# routev8_2.net
KiCad netlist of a schematic drawn in EAGLE
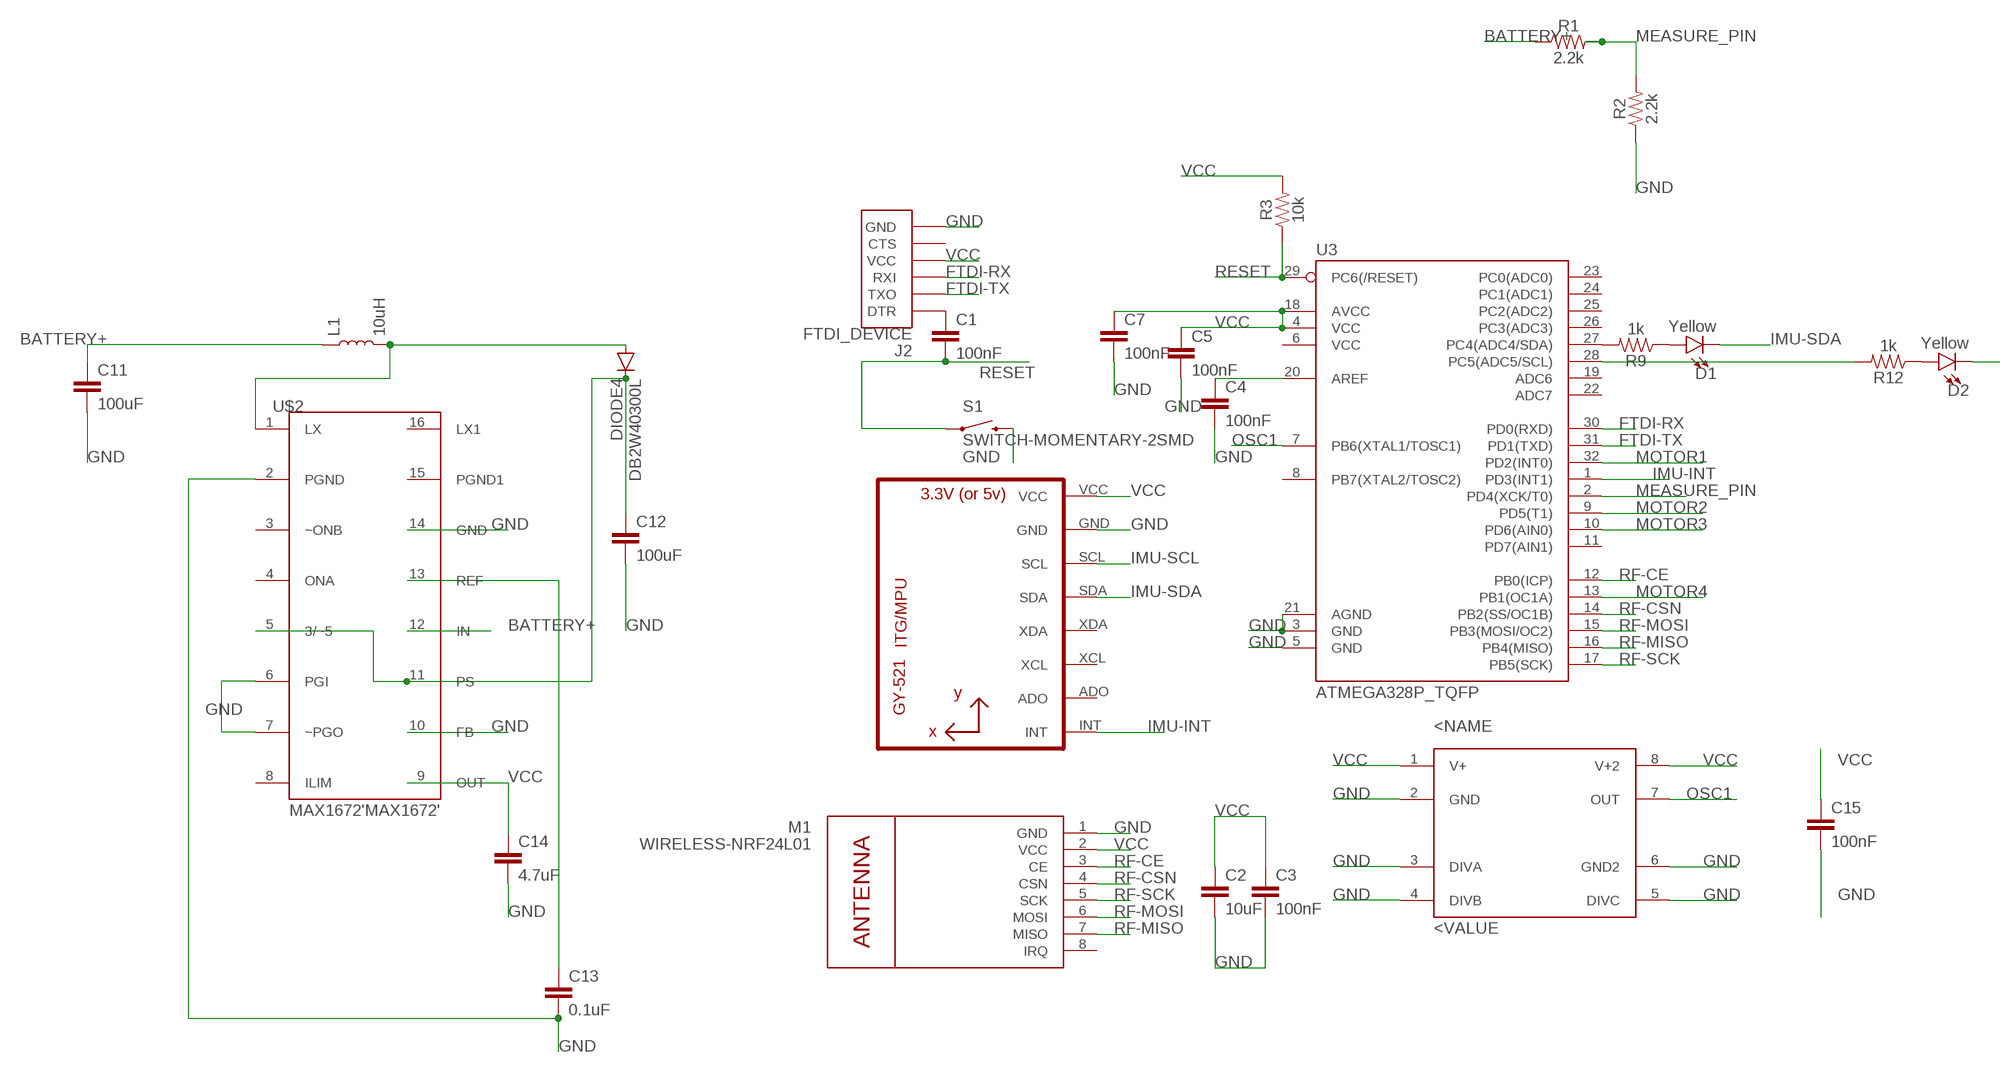
[diagram p0: schematic, sheet 1, part 1 of 2]
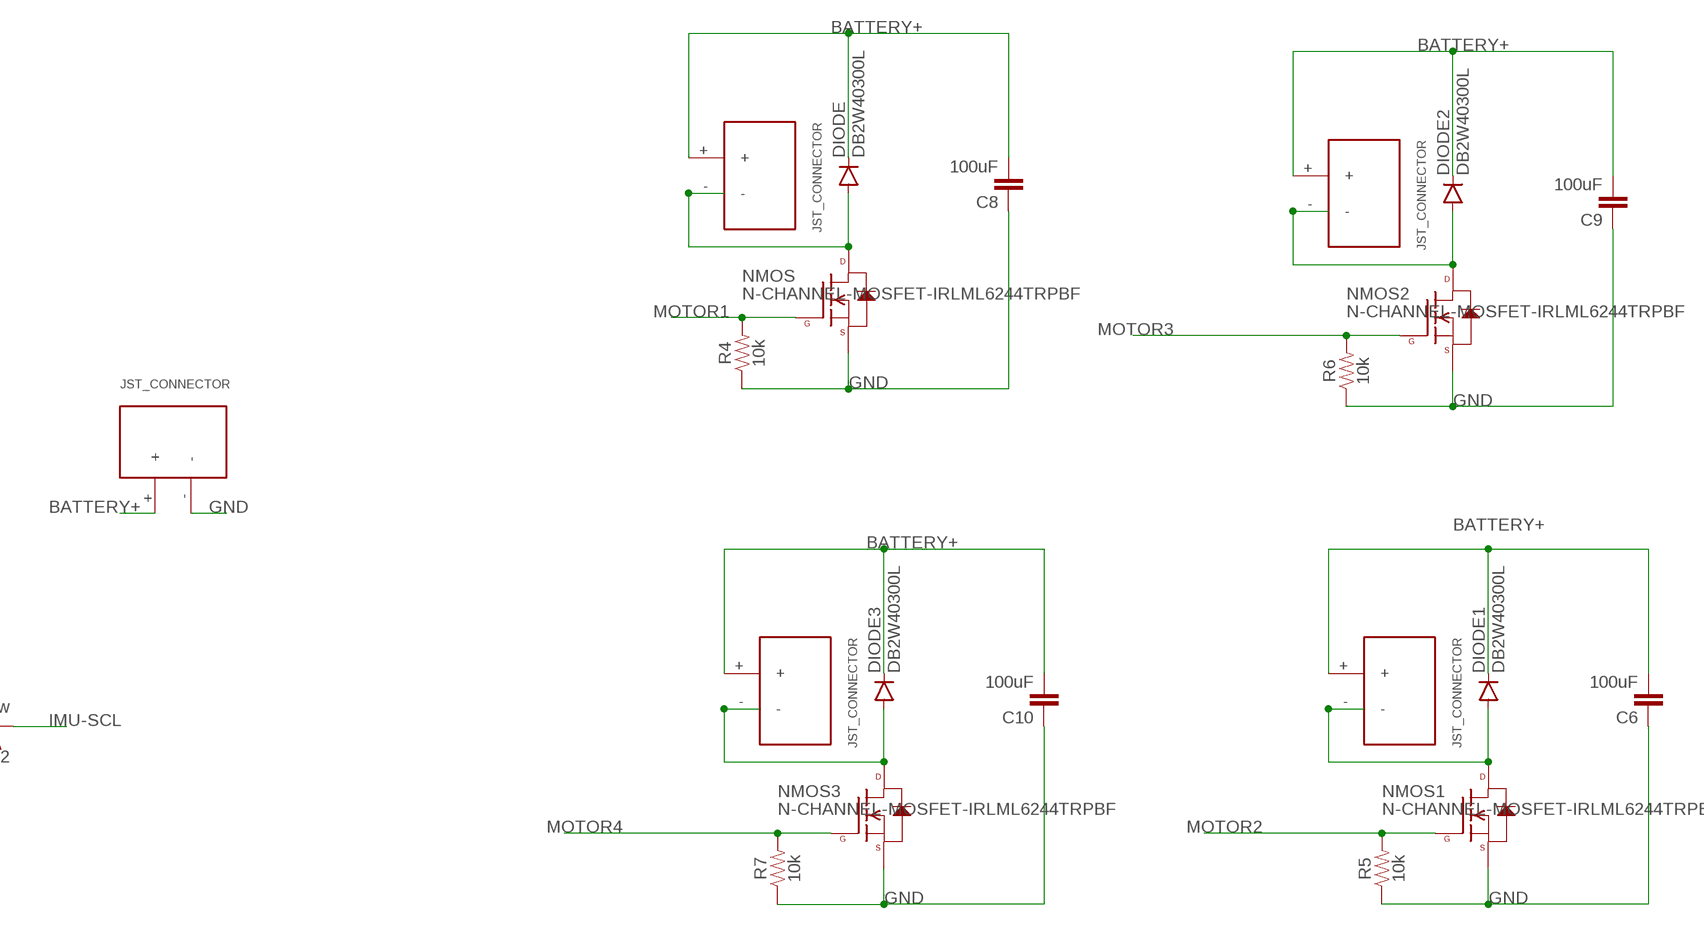
[diagram p1: schematic, sheet 1, part 2 of 2]

(export (version "E")
  (design (tool "Eeschema 10.0.6"))
  (components
    (comp (ref "C1")
      (value "100nF")
      (footprint "eagle-import:0603-CAP")
      (libsource (lib "eagle-import") (part "0.1UF-25V(+80/-20%)(0603)"))
    )
    (comp (ref "C2")
      (value "10uF")
      (footprint "eagle-import:0603-CAP")
      (libsource (lib "eagle-import") (part "CAP0603-CAP"))
    )
    (comp (ref "C3")
      (value "100nF")
      (footprint "eagle-import:0603-CAP")
      (libsource (lib "eagle-import") (part "CAP0603-CAP"))
    )
    (comp (ref "C4")
      (value "100nF")
      (footprint "eagle-import:0603-CAP")
      (libsource (lib "eagle-import") (part "CAP0603-CAP"))
    )
    (comp (ref "C5")
      (value "100nF")
      (footprint "eagle-import:0603-CAP")
      (libsource (lib "eagle-import") (part "CAP0603-CAP"))
    )
    (comp (ref "C6")
      (value "100uF")
      (footprint "eagle-import:0603-CAP")
      (libsource (lib "eagle-import") (part "CAP0603-CAP"))
    )
    (comp (ref "C7")
      (value "100nF")
      (footprint "eagle-import:0603-CAP")
      (libsource (lib "eagle-import") (part "CAP0603-CAP"))
    )
    (comp (ref "C8")
      (value "100uF")
      (footprint "eagle-import:0603-CAP")
      (libsource (lib "eagle-import") (part "CAP0603-CAP"))
    )
    (comp (ref "C9")
      (value "100uF")
      (footprint "eagle-import:0603-CAP")
      (libsource (lib "eagle-import") (part "CAP0603-CAP"))
    )
    (comp (ref "C10")
      (value "100uF")
      (footprint "eagle-import:0603-CAP")
      (libsource (lib "eagle-import") (part "CAP0603-CAP"))
    )
    (comp (ref "C11")
      (value "100uF")
      (footprint "eagle-import:0603-CAP")
      (libsource (lib "eagle-import") (part "CAP0603-CAP"))
    )
    (comp (ref "C12")
      (value "100uF")
      (footprint "eagle-import:0603-CAP")
      (libsource (lib "eagle-import") (part "CAP0603-CAP"))
    )
    (comp (ref "C13")
      (value "0.1uF")
      (footprint "eagle-import:0603-CAP")
      (libsource (lib "eagle-import") (part "CAP0603-CAP"))
    )
    (comp (ref "C14")
      (value "4.7uF")
      (footprint "eagle-import:0603-CAP")
      (libsource (lib "eagle-import") (part "CAP0603-CAP"))
    )
    (comp (ref "C15")
      (value "100nF")
      (footprint "eagle-import:0603-CAP")
      (libsource (lib "eagle-import") (part "0.1UF-25V(+80/-20%)(0603)"))
    )
    (comp (ref "D1")
      (value "Yellow")
      (footprint "eagle-import:LED-1206")
      (libsource (lib "eagle-import") (part "LED-YELLOWLILYPAD"))
    )
    (comp (ref "D2")
      (value "Yellow")
      (footprint "eagle-import:LED-1206")
      (libsource (lib "eagle-import") (part "LED-YELLOWLILYPAD"))
    )
    (comp (ref "DIODE")
      (value "DB2W40300L")
      (footprint "eagle-import:MINI2-F3-B")
      (libsource (lib "eagle-import") (part "DB2W40300L"))
    )
    (comp (ref "DIODE1")
      (value "DB2W40300L")
      (footprint "eagle-import:MINI2-F3-B")
      (libsource (lib "eagle-import") (part "DB2W40300L"))
    )
    (comp (ref "DIODE2")
      (value "DB2W40300L")
      (footprint "eagle-import:MINI2-F3-B")
      (libsource (lib "eagle-import") (part "DB2W40300L"))
    )
    (comp (ref "DIODE3")
      (value "DB2W40300L")
      (footprint "eagle-import:MINI2-F3-B")
      (libsource (lib "eagle-import") (part "DB2W40300L"))
    )
    (comp (ref "DIODE4")
      (value "DB2W40300L")
      (footprint "eagle-import:MINI2-F3-B")
      (libsource (lib "eagle-import") (part "DB2W40300L"))
    )
    (comp (ref "J2")
      (value "FTDI_DEVICE")
      (footprint "eagle-import:FTDI_DEVICE_SIDE")
      (libsource (lib "eagle-import") (part "FTDI_DEVICE"))
    )
    (comp (ref "L1")
      (value "10uH")
      (footprint "eagle-import:0603")
      (libsource (lib "eagle-import") (part "INDUCTOR-0603-33NH"))
    )
    (comp (ref "M1")
      (value "WIRELESS-NRF24L01")
      (footprint "eagle-import:WIRELESS-NRF24L01")
      (libsource (lib "eagle-import") (part "WIRELESS-NRF24L01"))
    )
    (comp (ref "MOTOR")
      (value "JST_CONNECTOR_FEMALE")
      (footprint "eagle-import:JST_CONNECTOR_FEMALE")
      (libsource (lib "eagle-import") (part "JST_CONNECTOR_FEMALE"))
    )
    (comp (ref "MOTOR1")
      (value "JST_CONNECTOR_FEMALE")
      (footprint "eagle-import:JST_CONNECTOR_FEMALE")
      (libsource (lib "eagle-import") (part "JST_CONNECTOR_FEMALE"))
    )
    (comp (ref "MOTOR2")
      (value "JST_CONNECTOR_FEMALE")
      (footprint "eagle-import:JST_CONNECTOR_FEMALE")
      (libsource (lib "eagle-import") (part "JST_CONNECTOR_FEMALE"))
    )
    (comp (ref "MOTOR3")
      (value "JST_CONNECTOR_FEMALE")
      (footprint "eagle-import:JST_CONNECTOR_FEMALE")
      (libsource (lib "eagle-import") (part "JST_CONNECTOR_FEMALE"))
    )
    (comp (ref "NMOS")
      (value "N-CHANNEL-MOSFET-IRLML6244TRPBF")
      (footprint "eagle-import:SOT23-3")
      (libsource (lib "eagle-import") (part "N-CHANNEL-MOSFET-IRLML6244TRPBF"))
    )
    (comp (ref "NMOS1")
      (value "N-CHANNEL-MOSFET-IRLML6244TRPBF")
      (footprint "eagle-import:SOT23-3")
      (libsource (lib "eagle-import") (part "N-CHANNEL-MOSFET-IRLML6244TRPBF"))
    )
    (comp (ref "NMOS2")
      (value "N-CHANNEL-MOSFET-IRLML6244TRPBF")
      (footprint "eagle-import:SOT23-3")
      (libsource (lib "eagle-import") (part "N-CHANNEL-MOSFET-IRLML6244TRPBF"))
    )
    (comp (ref "NMOS3")
      (value "N-CHANNEL-MOSFET-IRLML6244TRPBF")
      (footprint "eagle-import:SOT23-3")
      (libsource (lib "eagle-import") (part "N-CHANNEL-MOSFET-IRLML6244TRPBF"))
    )
    (comp (ref "R1")
      (value "2.2k")
      (footprint "eagle-import:0603")
      (libsource (lib "eagle-import") (part "2.2KOHM-0603-1/10W-1%"))
    )
    (comp (ref "R2")
      (value "2.2k")
      (footprint "eagle-import:0603")
      (libsource (lib "eagle-import") (part "2.2KOHM-0603-1/10W-1%"))
    )
    (comp (ref "R3")
      (value "10k")
      (footprint "eagle-import:0603")
      (libsource (lib "eagle-import") (part "2.2KOHM-0603-1/10W-1%"))
    )
    (comp (ref "R4")
      (value "10k")
      (footprint "eagle-import:0603")
      (libsource (lib "eagle-import") (part "2.2KOHM-0603-1/10W-1%"))
    )
    (comp (ref "R5")
      (value "10k")
      (footprint "eagle-import:0603")
      (libsource (lib "eagle-import") (part "2.2KOHM-0603-1/10W-1%"))
    )
    (comp (ref "R6")
      (value "10k")
      (footprint "eagle-import:0603")
      (libsource (lib "eagle-import") (part "2.2KOHM-0603-1/10W-1%"))
    )
    (comp (ref "R7")
      (value "10k")
      (footprint "eagle-import:0603")
      (libsource (lib "eagle-import") (part "2.2KOHM-0603-1/10W-1%"))
    )
    (comp (ref "R9")
      (value "1k")
      (footprint "eagle-import:0603")
      (libsource (lib "eagle-import") (part "2.2KOHM-0603-1/10W-1%"))
    )
    (comp (ref "R12")
      (value "1k")
      (footprint "eagle-import:0603")
      (libsource (lib "eagle-import") (part "2.2KOHM-0603-1/10W-1%"))
    )
    (comp (ref "S1")
      (value "SWITCH-MOMENTARY-2SMD")
      (footprint "eagle-import:TACTILE-SWITCH-SMD")
      (libsource (lib "eagle-import") (part "SWITCH-MOMENTARY-2SMD"))
    )
    (comp (ref "U$1")
      (value "JST_CONNECTOR_FEMALE")
      (footprint "eagle-import:JST_CONNECTOR_FEMALE")
      (libsource (lib "eagle-import") (part "JST_CONNECTOR_FEMALE"))
    )
    (comp (ref "U$2")
      (value "MAX1672'MAX1672'")
      (footprint "eagle-import:21-0055H_16")
      (libsource (lib "eagle-import") (part "MAX1672'MAX1672'"))
    )
    (comp (ref "U$3")
      (value "LTC6930CMS8-8.19LTC6930CMS8-8.19")
      (footprint "eagle-import:SOP65P490X110-8N")
      (libsource (lib "eagle-import") (part "LTC6930CMS8-8.19LTC6930CMS8-8.19"))
    )
    (comp (ref "U2")
      (value "GY-521MPU6050")
      (footprint "eagle-import:GY-521")
      (libsource (lib "eagle-import") (part "GY-521MPU6050"))
    )
    (comp (ref "U3")
      (value "ATMEGA328P_TQFP")
      (footprint "eagle-import:TQFP32-08")
      (libsource (lib "eagle-import") (part "ATMEGA328P_TQFP"))
    )
  )
  (nets
    (net (code "1") (name "BATTERY+") (class "Default")
      (node (ref "C10") (pin "2") (pinfunction "2_2") (pintype "passive"))
      (node (ref "C11") (pin "1") (pinfunction "1_1") (pintype "passive"))
      (node (ref "C6") (pin "2") (pinfunction "2_2") (pintype "passive"))
      (node (ref "C8") (pin "2") (pinfunction "2_2") (pintype "passive"))
      (node (ref "C9") (pin "2") (pinfunction "2_2") (pintype "passive"))
      (node (ref "DIODE") (pin "NEG") (pinfunction "GPIN_NEG") (pintype "passive"))
      (node (ref "DIODE1") (pin "NEG") (pinfunction "GPIN_NEG") (pintype "passive"))
      (node (ref "DIODE2") (pin "NEG") (pinfunction "GPIN_NEG") (pintype "passive"))
      (node (ref "DIODE3") (pin "NEG") (pinfunction "GPIN_NEG") (pintype "passive"))
      (node (ref "L1") (pin "1") (pinfunction "1_1") (pintype "passive"))
      (node (ref "MOTOR") (pin "+") (pinfunction "+_+") (pintype "bidirectional"))
      (node (ref "MOTOR1") (pin "+") (pinfunction "+_+") (pintype "bidirectional"))
      (node (ref "MOTOR2") (pin "+") (pinfunction "+_+") (pintype "bidirectional"))
      (node (ref "MOTOR3") (pin "+") (pinfunction "+_+") (pintype "bidirectional"))
      (node (ref "R1") (pin "1") (pinfunction "1_1") (pintype "passive"))
      (node (ref "U$1") (pin "+") (pinfunction "+_+") (pintype "bidirectional"))
      (node (ref "U$2") (pin "12") (pinfunction "IN_12") (pintype "bidirectional"))
    )
    (net (code "2") (name "FTDI-RX") (class "Default")
      (node (ref "J2") (pin "P$3") (pinfunction "RXI_P$3") (pintype "bidirectional"))
      (node (ref "U3") (pin "30") (pinfunction "PD0(RXD)_30") (pintype "bidirectional"))
    )
    (net (code "3") (name "FTDI-TX") (class "Default")
      (node (ref "J2") (pin "P$2") (pinfunction "TXO_P$2") (pintype "bidirectional"))
      (node (ref "U3") (pin "31") (pinfunction "PD1(TXD)_31") (pintype "bidirectional"))
    )
    (net (code "4") (name "GND") (class "Default")
      (node (ref "C10") (pin "1") (pinfunction "1_1") (pintype "passive"))
      (node (ref "C11") (pin "2") (pinfunction "2_2") (pintype "passive"))
      (node (ref "C12") (pin "2") (pinfunction "2_2") (pintype "passive"))
      (node (ref "C13") (pin "2") (pinfunction "2_2") (pintype "passive"))
      (node (ref "C14") (pin "2") (pinfunction "2_2") (pintype "passive"))
      (node (ref "C15") (pin "2") (pinfunction "2_2") (pintype "passive"))
      (node (ref "C2") (pin "2") (pinfunction "2_2") (pintype "passive"))
      (node (ref "C3") (pin "2") (pinfunction "2_2") (pintype "passive"))
      (node (ref "C4") (pin "2") (pinfunction "2_2") (pintype "passive"))
      (node (ref "C5") (pin "2") (pinfunction "2_2") (pintype "passive"))
      (node (ref "C6") (pin "1") (pinfunction "1_1") (pintype "passive"))
      (node (ref "C7") (pin "2") (pinfunction "2_2") (pintype "passive"))
      (node (ref "C8") (pin "1") (pinfunction "1_1") (pintype "passive"))
      (node (ref "C9") (pin "1") (pinfunction "1_1") (pintype "passive"))
      (node (ref "J2") (pin "P$6") (pinfunction "GND_P$6") (pintype "bidirectional"))
      (node (ref "M1") (pin "1") (pinfunction "GND_1") (pintype "power_in"))
      (node (ref "NMOS") (pin "2") (pinfunction "S_2") (pintype "passive"))
      (node (ref "NMOS1") (pin "2") (pinfunction "S_2") (pintype "passive"))
      (node (ref "NMOS2") (pin "2") (pinfunction "S_2") (pintype "passive"))
      (node (ref "NMOS3") (pin "2") (pinfunction "S_2") (pintype "passive"))
      (node (ref "R2") (pin "1") (pinfunction "1_1") (pintype "passive"))
      (node (ref "R4") (pin "1") (pinfunction "1_1") (pintype "passive"))
      (node (ref "R5") (pin "1") (pinfunction "1_1") (pintype "passive"))
      (node (ref "R6") (pin "1") (pinfunction "1_1") (pintype "passive"))
      (node (ref "R7") (pin "1") (pinfunction "1_1") (pintype "passive"))
      (node (ref "S1") (pin "3") (pinfunction "2_3") (pintype "passive"))
      (node (ref "U$1") (pin "-") (pinfunction "-_-") (pintype "bidirectional"))
      (node (ref "U$2") (pin "10") (pinfunction "FB_10") (pintype "bidirectional"))
      (node (ref "U$2") (pin "14") (pinfunction "GND_14") (pintype "bidirectional"))
      (node (ref "U$2") (pin "2") (pinfunction "PGND_2") (pintype "bidirectional"))
      (node (ref "U$2") (pin "6") (pinfunction "PGI_6") (pintype "bidirectional"))
      (node (ref "U$2") (pin "7") (pinfunction "~{PGO}_7") (pintype "bidirectional"))
      (node (ref "U$3") (pin "2") (pinfunction "GND_2") (pintype "bidirectional"))
      (node (ref "U$3") (pin "3") (pinfunction "DIVA_3") (pintype "bidirectional"))
      (node (ref "U$3") (pin "4") (pinfunction "DIVB_4") (pintype "bidirectional"))
      (node (ref "U$3") (pin "5") (pinfunction "DIVC_5") (pintype "bidirectional"))
      (node (ref "U$3") (pin "6") (pinfunction "GND2_6") (pintype "bidirectional"))
      (node (ref "U2") (pin "GND") (pinfunction "GND_GND") (pintype "bidirectional"))
      (node (ref "U3") (pin "21") (pinfunction "AGND_21") (pintype "bidirectional"))
      (node (ref "U3") (pin "3") (pinfunction "GND_3") (pintype "bidirectional"))
      (node (ref "U3") (pin "5") (pinfunction "GND_5") (pintype "bidirectional"))
    )
    (net (code "5") (name "IMU-INT") (class "Default")
      (node (ref "U2") (pin "INT") (pinfunction "INT_INT") (pintype "bidirectional"))
      (node (ref "U3") (pin "1") (pinfunction "PD3(INT1)_1") (pintype "bidirectional"))
    )
    (net (code "6") (name "IMU-SCL") (class "Default")
      (node (ref "D2") (pin "C") (pinfunction "C_C") (pintype "passive"))
      (node (ref "U2") (pin "SCL") (pinfunction "SCL_SCL") (pintype "bidirectional"))
    )
    (net (code "7") (name "IMU-SDA") (class "Default")
      (node (ref "D1") (pin "C") (pinfunction "C_C") (pintype "passive"))
      (node (ref "U2") (pin "SDA") (pinfunction "SDA_SDA") (pintype "bidirectional"))
    )
    (net (code "8") (name "MEASURE_PIN") (class "Default")
      (node (ref "R1") (pin "2") (pinfunction "2_2") (pintype "passive"))
      (node (ref "R2") (pin "2") (pinfunction "2_2") (pintype "passive"))
      (node (ref "U3") (pin "2") (pinfunction "PD4(XCK/T0)_2") (pintype "bidirectional"))
    )
    (net (code "9") (name "MOTOR1") (class "Default")
      (node (ref "NMOS") (pin "1") (pinfunction "G_1") (pintype "passive"))
      (node (ref "R4") (pin "2") (pinfunction "2_2") (pintype "passive"))
      (node (ref "U3") (pin "32") (pinfunction "PD2(INT0)_32") (pintype "bidirectional"))
    )
    (net (code "10") (name "MOTOR2") (class "Default")
      (node (ref "NMOS1") (pin "1") (pinfunction "G_1") (pintype "passive"))
      (node (ref "R5") (pin "2") (pinfunction "2_2") (pintype "passive"))
      (node (ref "U3") (pin "9") (pinfunction "PD5(T1)_9") (pintype "bidirectional"))
    )
    (net (code "11") (name "MOTOR3") (class "Default")
      (node (ref "NMOS2") (pin "1") (pinfunction "G_1") (pintype "passive"))
      (node (ref "R6") (pin "2") (pinfunction "2_2") (pintype "passive"))
      (node (ref "U3") (pin "10") (pinfunction "PD6(AIN0)_10") (pintype "bidirectional"))
    )
    (net (code "12") (name "MOTOR4") (class "Default")
      (node (ref "NMOS3") (pin "1") (pinfunction "G_1") (pintype "passive"))
      (node (ref "R7") (pin "2") (pinfunction "2_2") (pintype "passive"))
      (node (ref "U3") (pin "13") (pinfunction "PB1(OC1A)_13") (pintype "bidirectional"))
    )
    (net (code "13") (name "Net-(D1-PadA)") (class "Default")
      (node (ref "D1") (pin "A") (pinfunction "A_A") (pintype "passive"))
      (node (ref "R9") (pin "1") (pinfunction "1_1") (pintype "passive"))
    )
    (net (code "14") (name "Net-(D2-PadA)") (class "Default")
      (node (ref "D2") (pin "A") (pinfunction "A_A") (pintype "passive"))
      (node (ref "R12") (pin "1") (pinfunction "1_1") (pintype "passive"))
    )
    (net (code "15") (name "Net-(DIODE-PPIN)") (class "Default")
      (node (ref "DIODE") (pin "POS") (pinfunction "PPIN_POS") (pintype "passive"))
      (node (ref "MOTOR") (pin "-") (pinfunction "-_-") (pintype "bidirectional"))
      (node (ref "NMOS") (pin "3") (pinfunction "D_3") (pintype "passive"))
    )
    (net (code "16") (name "Net-(DIODE1-PPIN)") (class "Default")
      (node (ref "DIODE1") (pin "POS") (pinfunction "PPIN_POS") (pintype "passive"))
      (node (ref "MOTOR1") (pin "-") (pinfunction "-_-") (pintype "bidirectional"))
      (node (ref "NMOS1") (pin "3") (pinfunction "D_3") (pintype "passive"))
    )
    (net (code "17") (name "Net-(DIODE2-PPIN)") (class "Default")
      (node (ref "DIODE2") (pin "POS") (pinfunction "PPIN_POS") (pintype "passive"))
      (node (ref "MOTOR2") (pin "-") (pinfunction "-_-") (pintype "bidirectional"))
      (node (ref "NMOS2") (pin "3") (pinfunction "D_3") (pintype "passive"))
    )
    (net (code "18") (name "Net-(DIODE3-PPIN)") (class "Default")
      (node (ref "DIODE3") (pin "POS") (pinfunction "PPIN_POS") (pintype "passive"))
      (node (ref "MOTOR3") (pin "-") (pinfunction "-_-") (pintype "bidirectional"))
      (node (ref "NMOS3") (pin "3") (pinfunction "D_3") (pintype "passive"))
    )
    (net (code "19") (name "Net-(DIODE4-GPIN)") (class "Default")
      (node (ref "C12") (pin "1") (pinfunction "1_1") (pintype "passive"))
      (node (ref "DIODE4") (pin "NEG") (pinfunction "GPIN_NEG") (pintype "passive"))
      (node (ref "U$2") (pin "11") (pinfunction "PS_11") (pintype "bidirectional"))
      (node (ref "U$2") (pin "5") (pinfunction "3/~{5}_5") (pintype "bidirectional"))
    )
    (net (code "20") (name "Net-(DIODE4-PPIN)") (class "Default")
      (node (ref "DIODE4") (pin "POS") (pinfunction "PPIN_POS") (pintype "passive"))
      (node (ref "L1") (pin "2") (pinfunction "2_2") (pintype "passive"))
      (node (ref "U$2") (pin "1") (pinfunction "LX_1") (pintype "bidirectional"))
    )
    (net (code "21") (name "Net-(J2-DTR)") (class "Default")
      (node (ref "C1") (pin "1") (pinfunction "1_1") (pintype "passive"))
      (node (ref "J2") (pin "P$1") (pinfunction "DTR_P$1") (pintype "bidirectional"))
    )
    (net (code "22") (name "Net-(U$2-REF)") (class "Default")
      (node (ref "C13") (pin "1") (pinfunction "1_1") (pintype "passive"))
      (node (ref "U$2") (pin "13") (pinfunction "REF_13") (pintype "bidirectional"))
    )
    (net (code "23") (name "Net-(U3-AREF)") (class "Default")
      (node (ref "C4") (pin "1") (pinfunction "1_1") (pintype "passive"))
      (node (ref "U3") (pin "20") (pinfunction "AREF_20") (pintype "bidirectional"))
    )
    (net (code "24") (name "Net-(U3-PC4(ADC4{slash}SDA))") (class "Default")
      (node (ref "R9") (pin "2") (pinfunction "2_2") (pintype "passive"))
      (node (ref "U3") (pin "27") (pinfunction "PC4(ADC4/SDA)_27") (pintype "bidirectional"))
    )
    (net (code "25") (name "Net-(U3-PC5(ADC5{slash}SCL))") (class "Default")
      (node (ref "R12") (pin "2") (pinfunction "2_2") (pintype "passive"))
      (node (ref "U3") (pin "28") (pinfunction "PC5(ADC5/SCL)_28") (pintype "bidirectional"))
    )
    (net (code "26") (name "OSC1") (class "Default")
      (node (ref "U$3") (pin "7") (pinfunction "OUT_7") (pintype "bidirectional"))
      (node (ref "U3") (pin "7") (pinfunction "PB6(XTAL1/TOSC1)_7") (pintype "bidirectional"))
    )
    (net (code "27") (name "RESET") (class "Default")
      (node (ref "C1") (pin "2") (pinfunction "2_2") (pintype "passive"))
      (node (ref "R3") (pin "1") (pinfunction "1_1") (pintype "passive"))
      (node (ref "S1") (pin "1") (pinfunction "1_1") (pintype "passive"))
      (node (ref "U3") (pin "29") (pinfunction "PC6(/RESET)_29") (pintype "bidirectional"))
    )
    (net (code "28") (name "RF-CE") (class "Default")
      (node (ref "M1") (pin "3") (pinfunction "CE_3") (pintype "bidirectional"))
      (node (ref "U3") (pin "12") (pinfunction "PB0(ICP)_12") (pintype "bidirectional"))
    )
    (net (code "29") (name "RF-CSN") (class "Default")
      (node (ref "M1") (pin "4") (pinfunction "CSN_4") (pintype "bidirectional"))
      (node (ref "U3") (pin "14") (pinfunction "PB2(SS/OC1B)_14") (pintype "bidirectional"))
    )
    (net (code "30") (name "RF-MISO") (class "Default")
      (node (ref "M1") (pin "7") (pinfunction "MISO_7") (pintype "bidirectional"))
      (node (ref "U3") (pin "16") (pinfunction "PB4(MISO)_16") (pintype "bidirectional"))
    )
    (net (code "31") (name "RF-MOSI") (class "Default")
      (node (ref "M1") (pin "6") (pinfunction "MOSI_6") (pintype "bidirectional"))
      (node (ref "U3") (pin "15") (pinfunction "PB3(MOSI/OC2)_15") (pintype "bidirectional"))
    )
    (net (code "32") (name "RF-SCK") (class "Default")
      (node (ref "M1") (pin "5") (pinfunction "SCK_5") (pintype "bidirectional"))
      (node (ref "U3") (pin "17") (pinfunction "PB5(SCK)_17") (pintype "bidirectional"))
    )
    (net (code "33") (name "VCC") (class "Default")
      (node (ref "C14") (pin "1") (pinfunction "1_1") (pintype "passive"))
      (node (ref "C15") (pin "1") (pinfunction "1_1") (pintype "passive"))
      (node (ref "C2") (pin "1") (pinfunction "1_1") (pintype "passive"))
      (node (ref "C3") (pin "1") (pinfunction "1_1") (pintype "passive"))
      (node (ref "C5") (pin "1") (pinfunction "1_1") (pintype "passive"))
      (node (ref "C7") (pin "1") (pinfunction "1_1") (pintype "passive"))
      (node (ref "J2") (pin "P$4") (pinfunction "VCC_P$4") (pintype "bidirectional"))
      (node (ref "M1") (pin "2") (pinfunction "VCC_2") (pintype "power_in"))
      (node (ref "R3") (pin "2") (pinfunction "2_2") (pintype "passive"))
      (node (ref "U$2") (pin "9") (pinfunction "OUT_9") (pintype "bidirectional"))
      (node (ref "U$3") (pin "1") (pinfunction "V+_1") (pintype "bidirectional"))
      (node (ref "U$3") (pin "8") (pinfunction "V+2_8") (pintype "bidirectional"))
      (node (ref "U2") (pin "VCC") (pinfunction "VCC_VCC") (pintype "bidirectional"))
      (node (ref "U3") (pin "18") (pinfunction "AVCC_18") (pintype "bidirectional"))
      (node (ref "U3") (pin "4") (pinfunction "VCC_4") (pintype "bidirectional"))
    )
    (net (code "34") (name "unconnected-(J2-CTS-PadP$5)") (class "Default")
      (node (ref "J2") (pin "P$5") (pinfunction "CTS_P$5") (pintype "bidirectional"))
    )
    (net (code "35") (name "unconnected-(M1-IRQ-Pad8)") (class "Default")
      (node (ref "M1") (pin "8") (pinfunction "IRQ_8") (pintype "bidirectional"))
    )
    (net (code "36") (name "unconnected-(U$2-ILIM-Pad8)") (class "Default")
      (node (ref "U$2") (pin "8") (pinfunction "ILIM_8") (pintype "bidirectional"))
    )
    (net (code "37") (name "unconnected-(U$2-LX1-Pad16)") (class "Default")
      (node (ref "U$2") (pin "16") (pinfunction "LX1_16") (pintype "bidirectional"))
    )
    (net (code "38") (name "unconnected-(U$2-ONA-Pad4)") (class "Default")
      (node (ref "U$2") (pin "4") (pinfunction "ONA_4") (pintype "bidirectional"))
    )
    (net (code "39") (name "unconnected-(U$2-PGND1-Pad15)") (class "Default")
      (node (ref "U$2") (pin "15") (pinfunction "PGND1_15") (pintype "bidirectional"))
    )
    (net (code "40") (name "unconnected-(U$2-~{ONB}-Pad3)") (class "Default")
      (node (ref "U$2") (pin "3") (pinfunction "~{ONB}_3") (pintype "bidirectional"))
    )
    (net (code "41") (name "unconnected-(U2-PadADO)") (class "Default")
      (node (ref "U2") (pin "ADO") (pinfunction "ADO_ADO") (pintype "bidirectional"))
    )
    (net (code "42") (name "unconnected-(U2-PadXCL)") (class "Default")
      (node (ref "U2") (pin "XCL") (pinfunction "XCL_XCL") (pintype "bidirectional"))
    )
    (net (code "43") (name "unconnected-(U2-PadXDA)") (class "Default")
      (node (ref "U2") (pin "XDA") (pinfunction "XDA_XDA") (pintype "bidirectional"))
    )
    (net (code "44") (name "unconnected-(U3-ADC6-Pad19)") (class "Default")
      (node (ref "U3") (pin "19") (pinfunction "ADC6_19") (pintype "bidirectional"))
    )
    (net (code "45") (name "unconnected-(U3-ADC7-Pad22)") (class "Default")
      (node (ref "U3") (pin "22") (pinfunction "ADC7_22") (pintype "bidirectional"))
    )
    (net (code "46") (name "unconnected-(U3-PB7(XTAL2{slash}TOSC2)-Pad8)") (class "Default")
      (node (ref "U3") (pin "8") (pinfunction "PB7(XTAL2/TOSC2)_8") (pintype "bidirectional"))
    )
    (net (code "47") (name "unconnected-(U3-PC0(ADC0)-Pad23)") (class "Default")
      (node (ref "U3") (pin "23") (pinfunction "PC0(ADC0)_23") (pintype "bidirectional"))
    )
    (net (code "48") (name "unconnected-(U3-PC1(ADC1)-Pad24)") (class "Default")
      (node (ref "U3") (pin "24") (pinfunction "PC1(ADC1)_24") (pintype "bidirectional"))
    )
    (net (code "49") (name "unconnected-(U3-PC2(ADC2)-Pad25)") (class "Default")
      (node (ref "U3") (pin "25") (pinfunction "PC2(ADC2)_25") (pintype "bidirectional"))
    )
    (net (code "50") (name "unconnected-(U3-PC3(ADC3)-Pad26)") (class "Default")
      (node (ref "U3") (pin "26") (pinfunction "PC3(ADC3)_26") (pintype "bidirectional"))
    )
    (net (code "51") (name "unconnected-(U3-PD7(AIN1)-Pad11)") (class "Default")
      (node (ref "U3") (pin "11") (pinfunction "PD7(AIN1)_11") (pintype "bidirectional"))
    )
    (net (code "52") (name "unconnected-(U3-VCC-Pad6)") (class "Default")
      (node (ref "U3") (pin "6") (pinfunction "VCC_6") (pintype "bidirectional"))
    )
  )
)
